# FTDI.net
KiCad netlist of a schematic drawn in Altium Designer
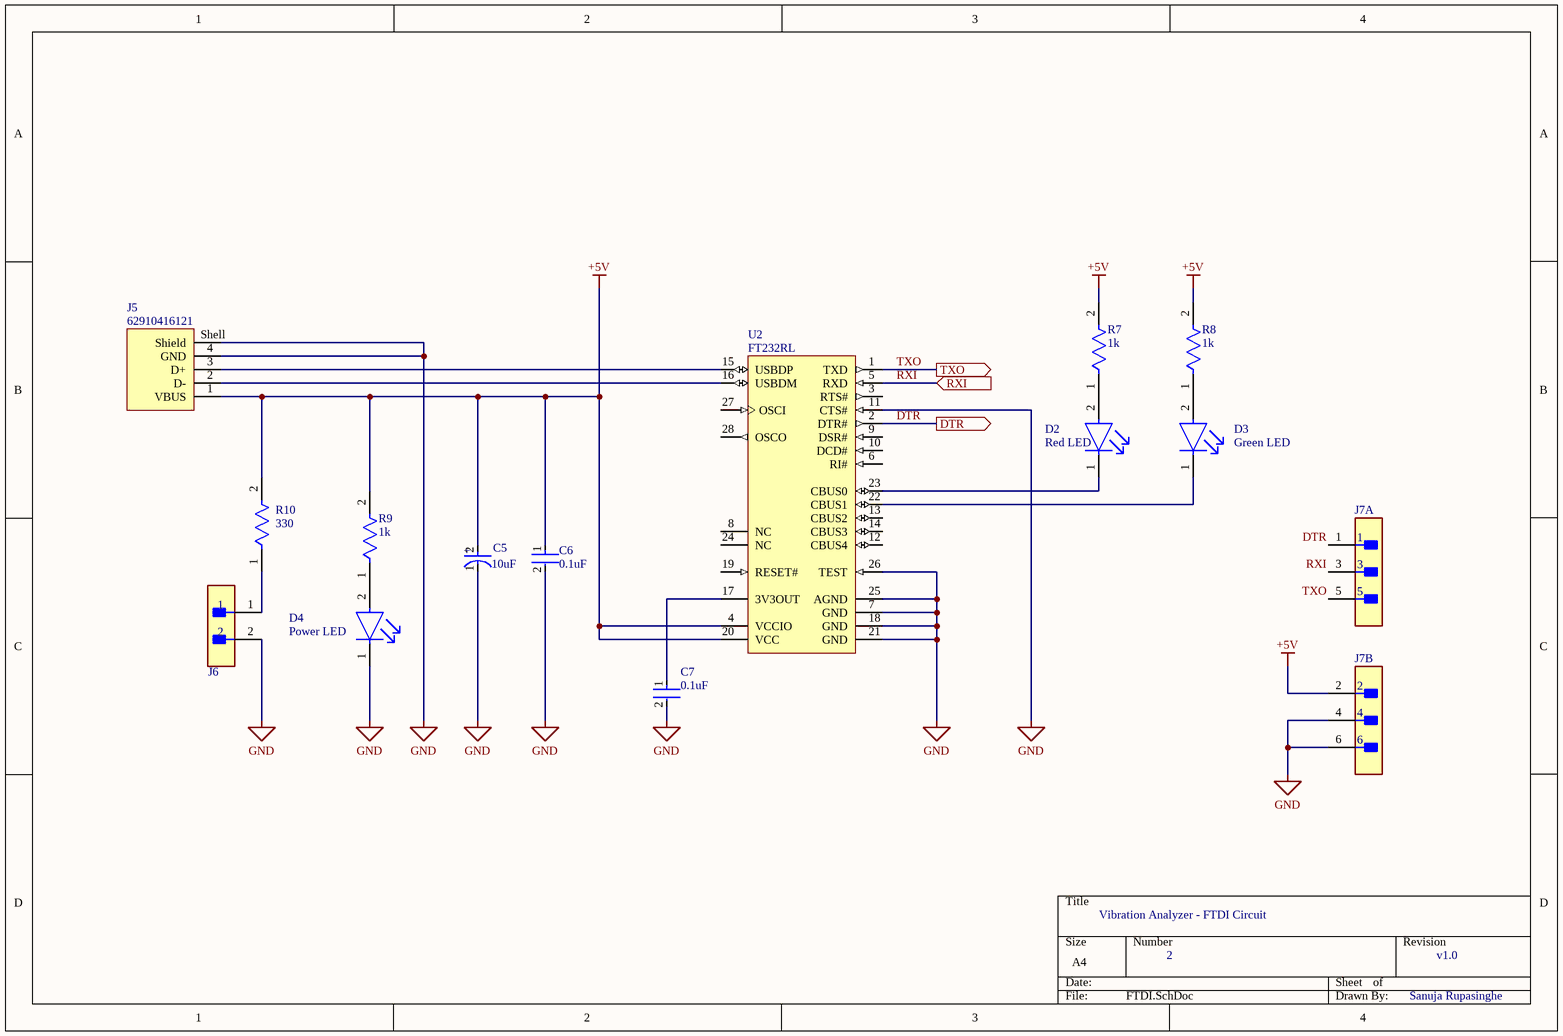
[diagram p0: FTDI.SchDoc]

(export (version "E")
  (design (tool "Eeschema 10.0.6"))
  (components
    (comp (ref "C5")
      (value "EEE1VA100SR")
      (footprint "FP-SC-MFG")
      (description "CAP ALUM 10UF 20% 35V SMD")
      (fields
        (field (name "CAPACITANCE") "10uF")
        (field (name "TOLERANCE") "20%")
        (field (name "VOLTAGE") "35V")
      )
      (libsource (lib "Altium Content Vault") (part "203bc49f2ac43e59fd269a8c329ed05"))
    )
    (comp (ref "C6")
      (value "GRM31M1X1H104JA01L")
      (footprint "FP-GRM31M-0_15-IPC_A")
      (fields
        (field (name "VOLTAGE") "50V")
        (field (name "TOLERANCE") "5%")
        (field (name "CAPACITANCE") "0.1uF")
      )
      (libsource (lib "Altium Content Vault") (part "b4654b650e69147ec39a6b967a45e02"))
    )
    (comp (ref "C7")
      (value "GRM31M1X1H104JA01L")
      (footprint "FP-GRM31M-0_15-IPC_A")
      (fields
        (field (name "VOLTAGE") "50V")
        (field (name "TOLERANCE") "5%")
        (field (name "CAPACITANCE") "0.1uF")
      )
      (libsource (lib "Altium Content Vault") (part "b4654b650e69147ec39a6b967a45e02"))
    )
    (comp (ref "D2")
      (value "HSMG-C150")
      (footprint "FP-HSMG-C150-MFG")
      (description "LED GREEN DIFFUSED 1206 SMD")
      (fields
        (field (name "MANUFACTURER") "Broadcom")
        (field (name "OCTOPART") "https://octopart.com/hsmg-c150-broadcom-71131304")
        (field (name "COLOR") "Red LED")
      )
      (libsource (lib "Altium Content Vault") (part "8706943c75ba83719d021d2fdc84c58"))
    )
    (comp (ref "D3")
      (value "HSMG-C150")
      (footprint "FP-HSMG-C150-MFG")
      (description "LED GREEN DIFFUSED 1206 SMD")
      (fields
        (field (name "MANUFACTURER") "Broadcom")
        (field (name "OCTOPART") "https://octopart.com/hsmg-c150-broadcom-71131304")
        (field (name "COLOR") "Green LED")
      )
      (libsource (lib "Altium Content Vault") (part "8706943c75ba83719d021d2fdc84c58"))
    )
    (comp (ref "D4")
      (value "HSMG-C150")
      (footprint "FP-HSMG-C150-MFG")
      (description "LED GREEN DIFFUSED 1206 SMD")
      (fields
        (field (name "MANUFACTURER") "Broadcom")
        (field (name "OCTOPART") "https://octopart.com/hsmg-c150-broadcom-71131304")
        (field (name "COLOR") "Power LED")
      )
      (libsource (lib "Altium Content Vault") (part "8706943c75ba83719d021d2fdc84c58"))
    )
    (comp (ref "J5")
      (value "62910416121")
      (footprint "62910416121")
      (libsource (lib "Altium Content Vault") (part "USB 2.0_Type B_Receptacle_1 Port"))
    )
    (comp (ref "J6")
      (value "B2B-XH-A(LF)(SN)")
      (footprint "FP-B2B-XH-A_LF_SN-MFG")
      (description "CONN HEADER VERT 2POS 2.5MM")
      (libsource (lib "Altium Content Vault") (part "3bc925449376181038e59eaffc5286c"))
    )
    (comp (ref "J7")
      (value "M20-9980346")
      (footprint "FP-M20-9980346-MFG")
      (description "CONN HEADER VERT 6POS 2.54MM")
      (fields
        (field (name "MANUFACTURER") "Harwin")
        (field (name "OCTOPART") "https://octopart.com/m20-9980346-harwin-5436545")
      )
      (libsource (lib "Altium Content Vault") (part "2654a11fb13586ecb194516b1c997bc"))
    )
    (comp (ref "R7")
      (value "MCR18EZPF30R0")
      (footprint "FP-MCR18-IPC_B")
      (description "Thick Film Chip Resistor, 1206, 30Ω, 1%, 100ppm/°C, 0.25W, 200V")
      (fields (field (name "RESISTANCE") "1k") (field (name "TOLERANCE") "1%"))
      (libsource (lib "Altium Content Vault") (part "1029c3af85768c4190bb7ad29bc67b5"))
    )
    (comp (ref "R8")
      (value "MCR18EZPF30R0")
      (footprint "FP-MCR18-IPC_B")
      (description "Thick Film Chip Resistor, 1206, 30Ω, 1%, 100ppm/°C, 0.25W, 200V")
      (fields (field (name "RESISTANCE") "1k") (field (name "TOLERANCE") "1%"))
      (libsource (lib "Altium Content Vault") (part "1029c3af85768c4190bb7ad29bc67b5"))
    )
    (comp (ref "R9")
      (value "MCR18EZPF30R0")
      (footprint "FP-MCR18-IPC_B")
      (description "Thick Film Chip Resistor, 1206, 30Ω, 1%, 100ppm/°C, 0.25W, 200V")
      (fields (field (name "RESISTANCE") "1k") (field (name "TOLERANCE") "1%"))
      (libsource (lib "Altium Content Vault") (part "1029c3af85768c4190bb7ad29bc67b5"))
    )
    (comp (ref "R10")
      (value "MCR18EZPF30R0")
      (footprint "FP-MCR18-IPC_B")
      (description "Thick Film Chip Resistor, 1206, 30Ω, 1%, 100ppm/°C, 0.25W, 200V")
      (fields (field (name "RESISTANCE") "330") (field (name "TOLERANCE") "1%"))
      (libsource (lib "Altium Content Vault") (part "1029c3af85768c4190bb7ad29bc67b5"))
    )
    (comp (ref "U2")
      (value "FT232RL")
      (footprint "FTDI-SSOP-28_M")
      (description "IC USB FS SERIAL UART 28-SSOP")
      (fields (field (name "MANUFACTURER") "FTDI"))
      (libsource (lib "Altium Content Vault") (part "FTDI-FT232-SSOP-28"))
    )
  )
  (nets
    (net (code "1") (name "+5V") (class "Default")
      (node (ref "C5") (pin "2") (pinfunction "A_2") (pintype "passive"))
      (node (ref "C6") (pin "1") (pinfunction "1_1") (pintype "passive"))
      (node (ref "J5") (pin "1") (pinfunction "VBUS_1") (pintype "passive"))
      (node (ref "J7") (pin "2") (pinfunction "2_2") (pintype "passive"))
      (node (ref "R10") (pin "2") (pinfunction "2_2") (pintype "passive"))
      (node (ref "R7") (pin "2") (pinfunction "2_2") (pintype "passive"))
      (node (ref "R8") (pin "2") (pinfunction "2_2") (pintype "passive"))
      (node (ref "R9") (pin "2") (pinfunction "2_2") (pintype "passive"))
      (node (ref "U2") (pin "20") (pinfunction "VCC_20") (pintype "power_in"))
      (node (ref "U2") (pin "4") (pinfunction "VCCIO_4") (pintype "power_in"))
    )
    (net (code "2") (name "/DTR") (class "Default")
      (node (ref "J7") (pin "1") (pinfunction "1_1") (pintype "passive"))
      (node (ref "U2") (pin "2") (pinfunction "DTR#_2") (pintype "output"))
    )
    (net (code "3") (name "/RXI") (class "Default")
      (node (ref "J7") (pin "3") (pinfunction "3_3") (pintype "passive"))
      (node (ref "U2") (pin "5") (pinfunction "RXD_5") (pintype "input"))
    )
    (net (code "4") (name "/TXO") (class "Default")
      (node (ref "J7") (pin "5") (pinfunction "5_5") (pintype "passive"))
      (node (ref "U2") (pin "1") (pinfunction "TXD_1") (pintype "output"))
    )
    (net (code "5") (name "GND") (class "Default")
      (node (ref "C5") (pin "1") (pinfunction "C_1") (pintype "passive"))
      (node (ref "C6") (pin "2") (pinfunction "2_2") (pintype "passive"))
      (node (ref "C7") (pin "2") (pinfunction "2_2") (pintype "passive"))
      (node (ref "D4") (pin "1") (pinfunction "C_1") (pintype "passive"))
      (node (ref "J5") (pin "4") (pinfunction "GND_4") (pintype "passive"))
      (node (ref "J5") (pin "Shell") (pinfunction "Shield_Shell") (pintype "passive"))
      (node (ref "J6") (pin "2") (pinfunction "2_2") (pintype "passive"))
      (node (ref "J7") (pin "4") (pinfunction "4_4") (pintype "passive"))
      (node (ref "J7") (pin "6") (pinfunction "6_6") (pintype "passive"))
      (node (ref "U2") (pin "11") (pinfunction "CTS#_11") (pintype "input"))
      (node (ref "U2") (pin "18") (pinfunction "GND_18") (pintype "power_in"))
      (node (ref "U2") (pin "21") (pinfunction "GND_21") (pintype "power_in"))
      (node (ref "U2") (pin "25") (pinfunction "AGND_25") (pintype "power_in"))
      (node (ref "U2") (pin "26") (pinfunction "TEST_26") (pintype "input"))
      (node (ref "U2") (pin "7") (pinfunction "GND_7") (pintype "power_in"))
    )
    (net (code "6") (name "Net-(D2-A)") (class "Default")
      (node (ref "D2") (pin "2") (pinfunction "A_2") (pintype "passive"))
      (node (ref "R7") (pin "1") (pinfunction "1_1") (pintype "passive"))
    )
    (net (code "7") (name "Net-(D2-C)") (class "Default")
      (node (ref "D2") (pin "1") (pinfunction "C_1") (pintype "passive"))
      (node (ref "U2") (pin "23") (pinfunction "CBUS0_23") (pintype "bidirectional"))
    )
    (net (code "8") (name "Net-(D3-A)") (class "Default")
      (node (ref "D3") (pin "2") (pinfunction "A_2") (pintype "passive"))
      (node (ref "R8") (pin "1") (pinfunction "1_1") (pintype "passive"))
    )
    (net (code "9") (name "Net-(D3-C)") (class "Default")
      (node (ref "D3") (pin "1") (pinfunction "C_1") (pintype "passive"))
      (node (ref "U2") (pin "22") (pinfunction "CBUS1_22") (pintype "bidirectional"))
    )
    (net (code "10") (name "Net-(D4-A)") (class "Default")
      (node (ref "D4") (pin "2") (pinfunction "A_2") (pintype "passive"))
      (node (ref "R9") (pin "1") (pinfunction "1_1") (pintype "passive"))
    )
    (net (code "11") (name "Net-(J5-D+)") (class "Default")
      (node (ref "J5") (pin "3") (pinfunction "D+_3") (pintype "passive"))
      (node (ref "U2") (pin "15") (pinfunction "USBDP_15") (pintype "bidirectional"))
    )
    (net (code "12") (name "Net-(J5-D-)") (class "Default")
      (node (ref "J5") (pin "2") (pinfunction "D-_2") (pintype "passive"))
      (node (ref "U2") (pin "16") (pinfunction "USBDM_16") (pintype "bidirectional"))
    )
    (net (code "13") (name "Net-(J6-Pad1)") (class "Default")
      (node (ref "J6") (pin "1") (pinfunction "1_1") (pintype "passive"))
      (node (ref "R10") (pin "1") (pinfunction "1_1") (pintype "passive"))
    )
    (net (code "14") (name "Net-(U2-3V3OUT)") (class "Default")
      (node (ref "C7") (pin "1") (pinfunction "1_1") (pintype "passive"))
      (node (ref "U2") (pin "17") (pinfunction "3V3OUT_17") (pintype "power_in"))
    )
    (net (code "15") (name "unconnected-(U2-CBUS2-Pad13)") (class "Default")
      (node (ref "U2") (pin "13") (pinfunction "CBUS2_13") (pintype "bidirectional"))
    )
    (net (code "16") (name "unconnected-(U2-CBUS3-Pad14)") (class "Default")
      (node (ref "U2") (pin "14") (pinfunction "CBUS3_14") (pintype "bidirectional"))
    )
    (net (code "17") (name "unconnected-(U2-CBUS4-Pad12)") (class "Default")
      (node (ref "U2") (pin "12") (pinfunction "CBUS4_12") (pintype "bidirectional"))
    )
    (net (code "18") (name "unconnected-(U2-DCD#-Pad10)") (class "Default")
      (node (ref "U2") (pin "10") (pinfunction "DCD#_10") (pintype "input"))
    )
    (net (code "19") (name "unconnected-(U2-DSR#-Pad9)") (class "Default")
      (node (ref "U2") (pin "9") (pinfunction "DSR#_9") (pintype "input"))
    )
    (net (code "20") (name "unconnected-(U2-NC-Pad8)") (class "Default")
      (node (ref "U2") (pin "8") (pinfunction "NC_8") (pintype "passive"))
    )
    (net (code "21") (name "unconnected-(U2-NC-Pad24)") (class "Default")
      (node (ref "U2") (pin "24") (pinfunction "NC_24") (pintype "passive"))
    )
    (net (code "22") (name "unconnected-(U2-OSCI-Pad27)") (class "Default")
      (node (ref "U2") (pin "27") (pinfunction "OSCI_27") (pintype "input"))
    )
    (net (code "23") (name "unconnected-(U2-OSCO-Pad28)") (class "Default")
      (node (ref "U2") (pin "28") (pinfunction "OSCO_28") (pintype "output"))
    )
    (net (code "24") (name "unconnected-(U2-RESET#-Pad19)") (class "Default")
      (node (ref "U2") (pin "19") (pinfunction "RESET#_19") (pintype "input"))
    )
    (net (code "25") (name "unconnected-(U2-RI#-Pad6)") (class "Default")
      (node (ref "U2") (pin "6") (pinfunction "RI#_6") (pintype "input"))
    )
    (net (code "26") (name "unconnected-(U2-RTS#-Pad3)") (class "Default")
      (node (ref "U2") (pin "3") (pinfunction "RTS#_3") (pintype "output"))
    )
  )
)
